# control.net
KiCad netlist of a schematic drawn in EAGLE
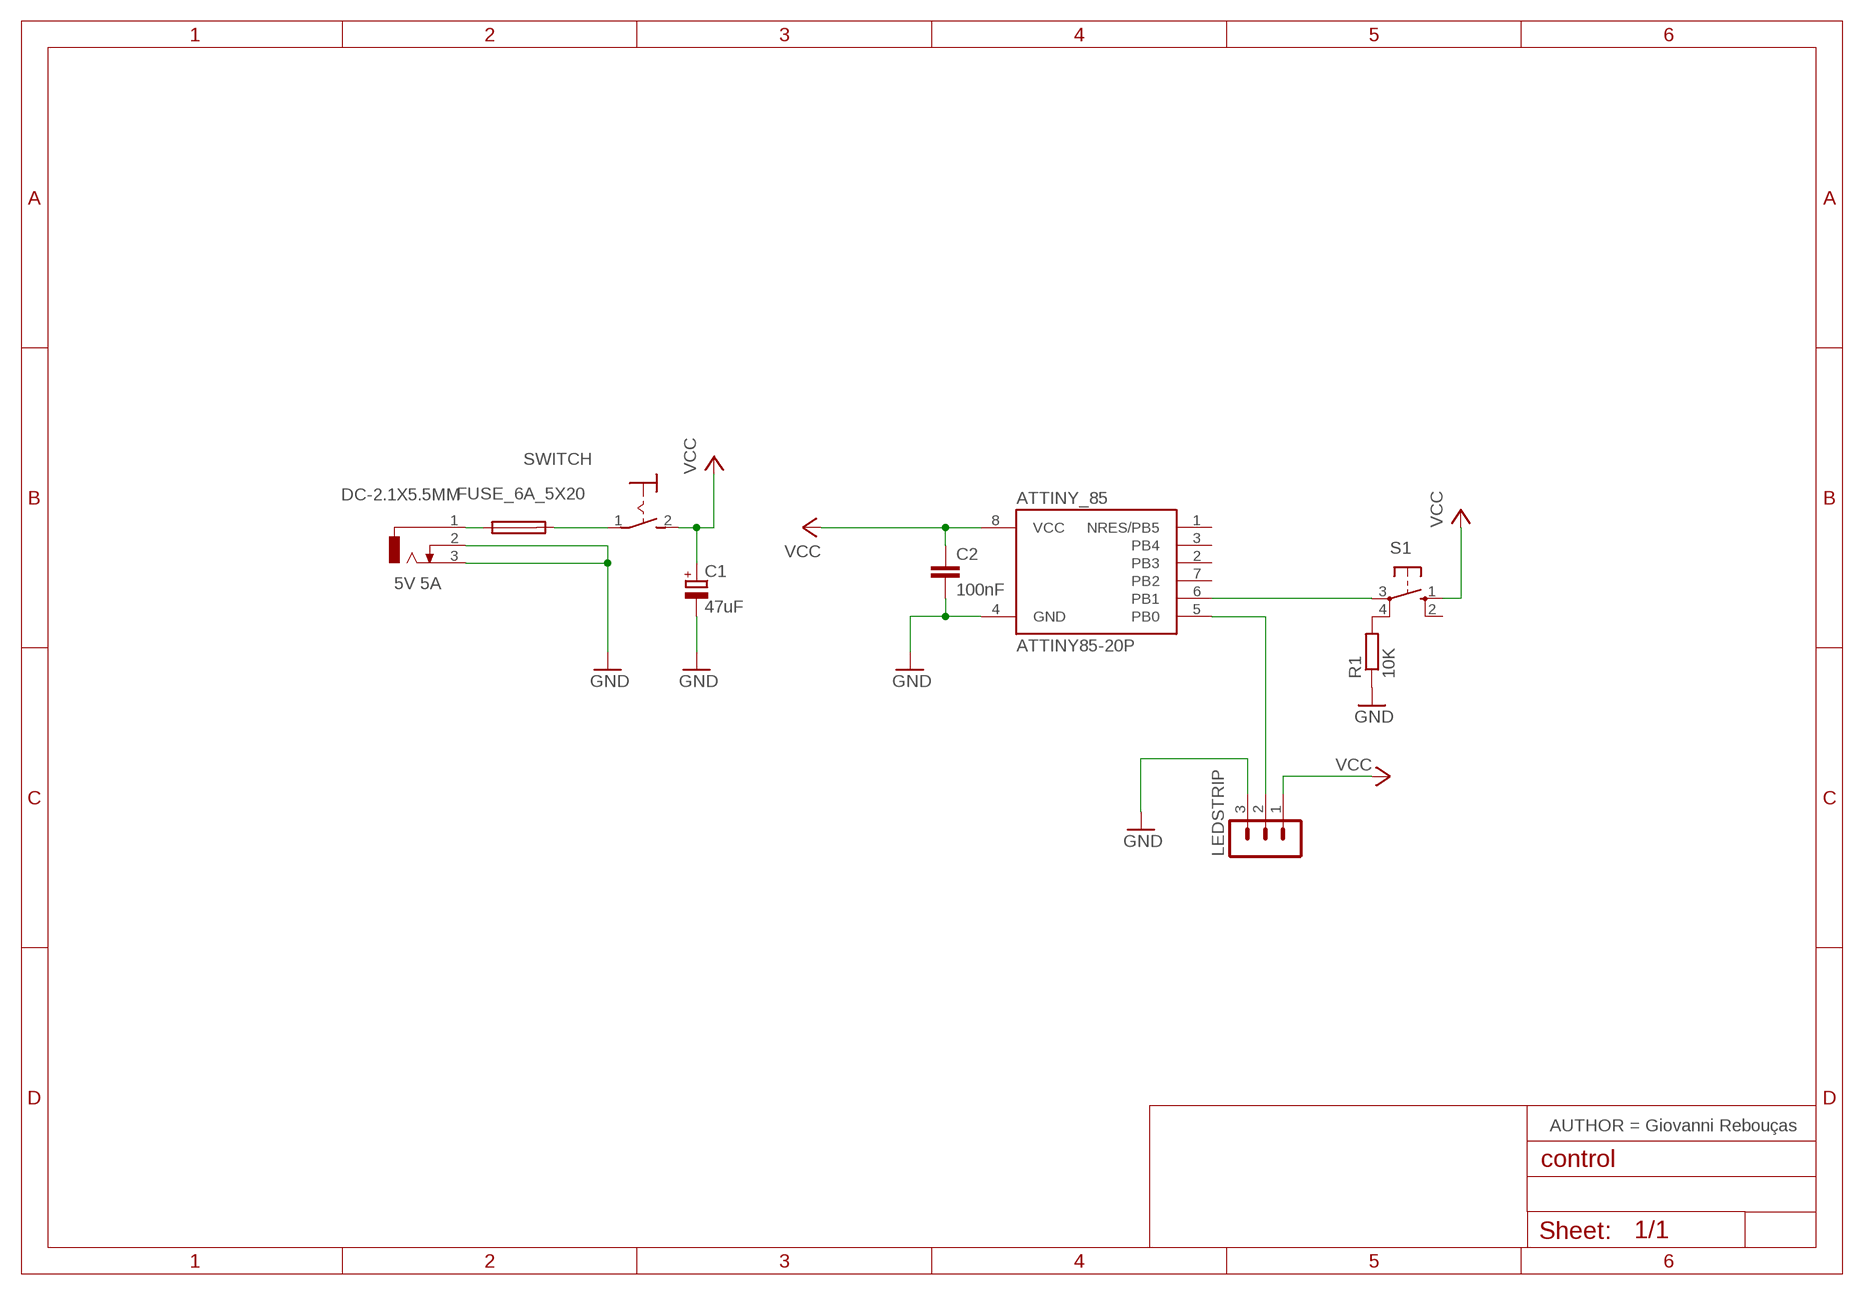
[diagram p0: schematic, sheet 1]

(export (version "E")
  (design (tool "Eeschema 10.0.6"))
  (components
    (comp (ref "ATTINY_85")
      (value "ATTINY85-20P")
      (footprint "eagle-import:PDIP08_300MIL")
      (libsource (lib "eagle-import") (part "ATTINY85P-20"))
    )
    (comp (ref "C1")
      (value "47uF")
      (footprint "eagle-import:E3,5-10")
      (libsource (lib "eagle-import") (part "CPOL-EUE3.5-10"))
    )
    (comp (ref "C2")
      (value "100nF")
      (footprint "eagle-import:C025-025X050")
      (libsource (lib "eagle-import") (part "C-EU025-025X050"))
    )
    (comp (ref "DC-2.1X5.5MM")
      (value "5V 5A")
      (footprint "eagle-import:DCJ0303")
      (libsource (lib "eagle-import") (part "DCJ0303"))
    )
    (comp (ref "FUSE_6A_5X20")
      (value "FUSEBLANK_5X20MM")
      (footprint "eagle-import:FUSE_HOLDER_5X20MM")
      (libsource (lib "eagle-import") (part "FUSEBLANK_5X20MM"))
    )
    (comp (ref "LEDSTRIP")
      (value "MA03-1")
      (footprint "eagle-import:MA03-1")
      (libsource (lib "eagle-import") (part "MA03-1"))
    )
    (comp (ref "R1")
      (value "10K")
      (footprint "eagle-import:0207_10")
      (libsource (lib "eagle-import") (part "R-EU_0207/10"))
    )
    (comp (ref "S1")
      (value "10-XX")
      (footprint "eagle-import:B3F-10XX")
      (fields (field (name "MPN") "B3F-1000"))
      (libsource (lib "eagle-import") (part "10-XX"))
    )
    (comp (ref "SWITCH")
      (value "MS243")
      (footprint "eagle-import:MS243")
      (libsource (lib "eagle-import") (part "MS243"))
    )
  )
  (nets
    (net (code "1") (name "GND") (class "Default")
      (node (ref "ATTINY_85") (pin "4") (pinfunction "GND_4") (pintype "power_in"))
      (node (ref "C1") (pin "-") (pinfunction "-_-") (pintype "passive"))
      (node (ref "C2") (pin "2") (pinfunction "2_2") (pintype "passive"))
      (node (ref "DC-2.1X5.5MM") (pin "2") (pinfunction "2_2") (pintype "passive"))
      (node (ref "DC-2.1X5.5MM") (pin "3") (pinfunction "3_3") (pintype "passive"))
      (node (ref "LEDSTRIP") (pin "3") (pinfunction "3_3") (pintype "passive"))
      (node (ref "R1") (pin "1") (pinfunction "1_1") (pintype "passive"))
    )
    (net (code "2") (name "Net-(ATTINY_85-PB0)") (class "Default")
      (node (ref "ATTINY_85") (pin "5") (pinfunction "PB0_5") (pintype "bidirectional"))
      (node (ref "LEDSTRIP") (pin "2") (pinfunction "2_2") (pintype "passive"))
    )
    (net (code "3") (name "Net-(ATTINY_85-PB1)") (class "Default")
      (node (ref "ATTINY_85") (pin "6") (pinfunction "PB1_6") (pintype "bidirectional"))
      (node (ref "S1") (pin "3") (pinfunction "P_3") (pintype "passive"))
    )
    (net (code "4") (name "Net-(DC-2.1X5.5MM-Pad1)") (class "Default")
      (node (ref "DC-2.1X5.5MM") (pin "1") (pinfunction "1_1") (pintype "passive"))
      (node (ref "FUSE_6A_5X20") (pin "1") (pinfunction "1_1") (pintype "passive"))
    )
    (net (code "5") (name "Net-(S1-P1)") (class "Default")
      (node (ref "R1") (pin "2") (pinfunction "2_2") (pintype "passive"))
      (node (ref "S1") (pin "4") (pinfunction "P1_4") (pintype "passive"))
    )
    (net (code "6") (name "Net-(SWITCH-P)") (class "Default")
      (node (ref "FUSE_6A_5X20") (pin "2") (pinfunction "2_2") (pintype "passive"))
      (node (ref "SWITCH") (pin "1") (pinfunction "P_1") (pintype "passive"))
    )
    (net (code "7") (name "VCC") (class "Default")
      (node (ref "ATTINY_85") (pin "8") (pinfunction "VCC_8") (pintype "power_in"))
      (node (ref "C1") (pin "+") (pinfunction "+_+") (pintype "passive"))
      (node (ref "C2") (pin "1") (pinfunction "1_1") (pintype "passive"))
      (node (ref "LEDSTRIP") (pin "1") (pinfunction "1_1") (pintype "passive"))
      (node (ref "S1") (pin "1") (pinfunction "S_1") (pintype "passive"))
      (node (ref "SWITCH") (pin "2") (pinfunction "S_2") (pintype "passive"))
    )
    (net (code "8") (name "unconnected-(ATTINY_85-NRES{slash}PB5-Pad1)") (class "Default")
      (node (ref "ATTINY_85") (pin "1") (pinfunction "NRES/PB5_1") (pintype "bidirectional"))
    )
    (net (code "9") (name "unconnected-(ATTINY_85-PB2-Pad7)") (class "Default")
      (node (ref "ATTINY_85") (pin "7") (pinfunction "PB2_7") (pintype "bidirectional"))
    )
    (net (code "10") (name "unconnected-(ATTINY_85-PB3-Pad2)") (class "Default")
      (node (ref "ATTINY_85") (pin "2") (pinfunction "PB3_2") (pintype "bidirectional"))
    )
    (net (code "11") (name "unconnected-(ATTINY_85-PB4-Pad3)") (class "Default")
      (node (ref "ATTINY_85") (pin "3") (pinfunction "PB4_3") (pintype "bidirectional"))
    )
    (net (code "12") (name "unconnected-(S1-S1-Pad2)") (class "Default")
      (node (ref "S1") (pin "2") (pinfunction "S1_2") (pintype "passive"))
    )
  )
)
